# EEROS_Sensorplatine.net
KiCad netlist of a schematic drawn in Altium Designer
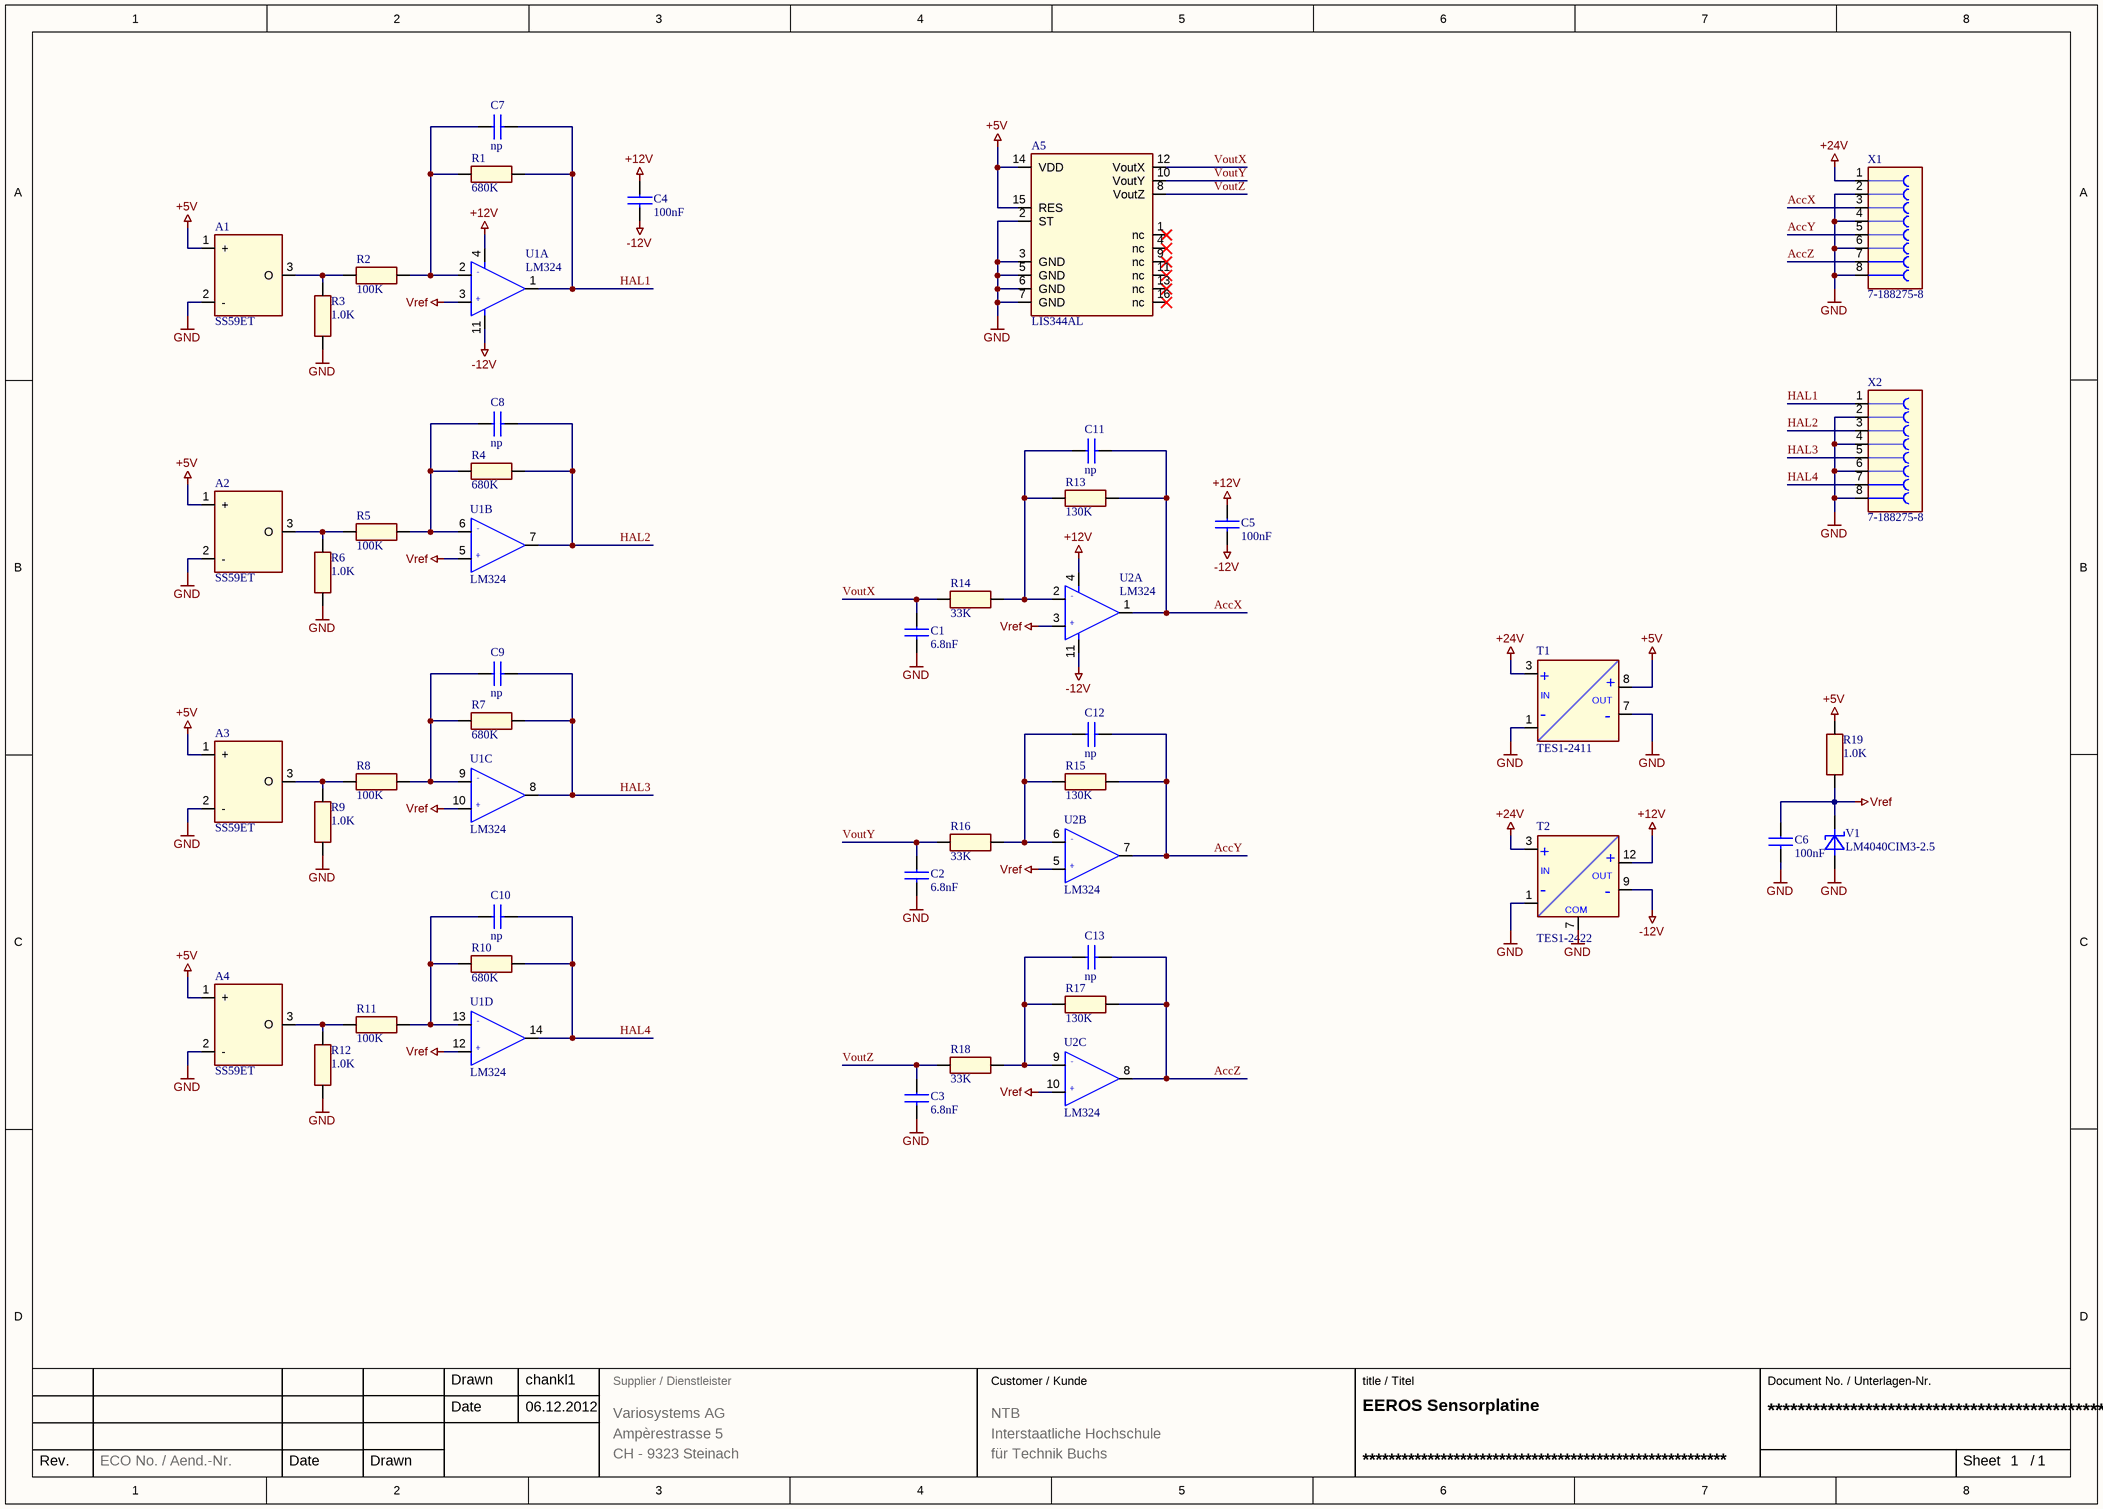
[diagram p0: EEROS_Sensorplatine.SchDoc]

(export (version "E")
  (design (tool "Eeschema 10.0.6"))
  (components
    (comp (ref "A1")
      (value "SS59ET")
      (footprint "SM/SOT89_1234")
      (description "S_ SEN MAGNE SS59ET_________________ ___")
      (fields (field (name "PART NUMBER") "2024317") (field (name "MANUFACTURER") "Honeywell"))
      (libsource (lib "Database") (part "SS59ET"))
    )
    (comp (ref "A2")
      (value "SS59ET")
      (footprint "SM/SOT89_1234")
      (description "S_ SEN MAGNE SS59ET_________________ ___")
      (fields (field (name "PART NUMBER") "2024317") (field (name "MANUFACTURER") "Honeywell"))
      (libsource (lib "Database") (part "SS59ET"))
    )
    (comp (ref "A3")
      (value "SS59ET")
      (footprint "SM/SOT89_1234")
      (description "S_ SEN MAGNE SS59ET_________________ ___")
      (fields (field (name "PART NUMBER") "2024317") (field (name "MANUFACTURER") "Honeywell"))
      (libsource (lib "Database") (part "SS59ET"))
    )
    (comp (ref "A4")
      (value "SS59ET")
      (footprint "SM/SOT89_1234")
      (description "S_ SEN MAGNE SS59ET_________________ ___")
      (fields (field (name "PART NUMBER") "2024317") (field (name "MANUFACTURER") "Honeywell"))
      (libsource (lib "Database") (part "SS59ET"))
    )
    (comp (ref "A5")
      (value "LIS344AL")
      (footprint "QFN.65M/16/WG4.00")
      (description "S_ SEN ACCEL LIS344AL_______________ ___")
      (fields (field (name "PART NUMBER") "2024318") (field (name "MANUFACTURER") "STMicrolectronics"))
      (libsource (lib "Database") (part "LIS344AL"))
    )
    (comp (ref "C1")
      (value "6.8nF")
      (footprint "VS-CAPACITORS-000A:SM/C_0603_REFLOW")
      (description "SC CAP __0603 __6n80 _50V ___10% X7R ___")
      (fields (field (name "PART NUMBER") "239551") (field (name "VOLTAGE") "50V"))
      (libsource (lib "Database") (part "CAP NP"))
    )
    (comp (ref "C2")
      (value "6.8nF")
      (footprint "VS-CAPACITORS-000A:SM/C_0603_REFLOW")
      (description "SC CAP __0603 __6n80 _50V ___10% X7R ___")
      (fields (field (name "PART NUMBER") "239551") (field (name "VOLTAGE") "50V"))
      (libsource (lib "Database") (part "CAP NP"))
    )
    (comp (ref "C3")
      (value "6.8nF")
      (footprint "VS-CAPACITORS-000A:SM/C_0603_REFLOW")
      (description "SC CAP __0603 __6n80 _50V ___10% X7R ___")
      (fields (field (name "PART NUMBER") "239551") (field (name "VOLTAGE") "50V"))
      (libsource (lib "Database") (part "CAP NP"))
    )
    (comp (ref "C4")
      (value "100nF")
      (footprint "VS-CAPACITORS-000A:SM/C_0603_REFLOW")
      (description "SC CAP __0603 100N00 _25V 80/20% Y5V ___")
      (fields (field (name "PART NUMBER") "208013") (field (name "VOLTAGE") "25V"))
      (libsource (lib "Database") (part "CAP NP"))
    )
    (comp (ref "C5")
      (value "100nF")
      (footprint "VS-CAPACITORS-000A:SM/C_0603_REFLOW")
      (description "SC CAP __0603 100N00 _25V 80/20% Y5V ___")
      (fields (field (name "PART NUMBER") "208013") (field (name "VOLTAGE") "25V"))
      (libsource (lib "Database") (part "CAP NP"))
    )
    (comp (ref "C6")
      (value "100nF")
      (footprint "VS-CAPACITORS-000A:SM/C_0603_REFLOW")
      (description "SC CAP __0603 100N00 _25V 80/20% Y5V ___")
      (fields (field (name "PART NUMBER") "208013") (field (name "VOLTAGE") "25V"))
      (libsource (lib "Database") (part "CAP NP"))
    )
    (comp (ref "C7")
      (value "np")
      (footprint "VS-CAPACITORS-000A:SM/C_0603_REFLOW")
      (libsource (lib "VS-CAPACITORS-000A") (part "CAP NP"))
    )
    (comp (ref "C8")
      (value "np")
      (footprint "VS-CAPACITORS-000A:SM/C_0603_REFLOW")
      (libsource (lib "VS-CAPACITORS-000A") (part "CAP NP"))
    )
    (comp (ref "C9")
      (value "np")
      (footprint "VS-CAPACITORS-000A:SM/C_0603_REFLOW")
      (libsource (lib "VS-CAPACITORS-000A") (part "CAP NP"))
    )
    (comp (ref "C10")
      (value "np")
      (footprint "VS-CAPACITORS-000A:SM/C_0603_REFLOW")
      (libsource (lib "VS-CAPACITORS-000A") (part "CAP NP"))
    )
    (comp (ref "C11")
      (value "np")
      (footprint "VS-CAPACITORS-000A:SM/C_0603_REFLOW")
      (libsource (lib "VS-CAPACITORS-000A") (part "CAP NP"))
    )
    (comp (ref "C12")
      (value "np")
      (footprint "VS-CAPACITORS-000A:SM/C_0603_REFLOW")
      (libsource (lib "VS-CAPACITORS-000A") (part "CAP NP"))
    )
    (comp (ref "C13")
      (value "np")
      (footprint "VS-CAPACITORS-000A:SM/C_0603_REFLOW")
      (libsource (lib "VS-CAPACITORS-000A") (part "CAP NP"))
    )
    (comp (ref "R1")
      (value "680K")
      (footprint "VS-PASSIVES-000A:SM/R_0603_REFLOW")
      (description "SC RES __0603 680K00 __0W1 ___1% T100 __")
      (fields (field (name "PART NUMBER") "226186") (field (name "POWER") "0.1W"))
      (libsource (lib "Database") (part "R-DIN"))
    )
    (comp (ref "R2")
      (value "100K")
      (footprint "VS-PASSIVES-000A:SM/R_0603_REFLOW")
      (description "SC RES __0603 100K00 __0W1 ___1% T100 __")
      (fields (field (name "PART NUMBER") "200141") (field (name "POWER") "0.1W"))
      (libsource (lib "Database") (part "R-DIN"))
    )
    (comp (ref "R3")
      (value "1.0K")
      (footprint "VS-PASSIVES-000A:SM/R_0603_REFLOW")
      (description "SC RES __0603 __1K00 __0W1 ___1% T100 __")
      (fields (field (name "PART NUMBER") "200139") (field (name "POWER") "0.1W"))
      (libsource (lib "") (part "R-DIN_1"))
    )
    (comp (ref "R4")
      (value "680K")
      (footprint "VS-PASSIVES-000A:SM/R_0603_REFLOW")
      (description "SC RES __0603 680K00 __0W1 ___1% T100 __")
      (fields (field (name "PART NUMBER") "226186") (field (name "POWER") "0.1W"))
      (libsource (lib "Database") (part "R-DIN"))
    )
    (comp (ref "R5")
      (value "100K")
      (footprint "VS-PASSIVES-000A:SM/R_0603_REFLOW")
      (description "SC RES __0603 100K00 __0W1 ___1% T100 __")
      (fields (field (name "PART NUMBER") "200141") (field (name "POWER") "0.1W"))
      (libsource (lib "Database") (part "R-DIN"))
    )
    (comp (ref "R6")
      (value "1.0K")
      (footprint "VS-PASSIVES-000A:SM/R_0603_REFLOW")
      (description "SC RES __0603 __1K00 __0W1 ___1% T100 __")
      (fields (field (name "PART NUMBER") "200139") (field (name "POWER") "0.1W"))
      (libsource (lib "") (part "R-DIN_1"))
    )
    (comp (ref "R7")
      (value "680K")
      (footprint "VS-PASSIVES-000A:SM/R_0603_REFLOW")
      (description "SC RES __0603 680K00 __0W1 ___1% T100 __")
      (fields (field (name "PART NUMBER") "226186") (field (name "POWER") "0.1W"))
      (libsource (lib "Database") (part "R-DIN"))
    )
    (comp (ref "R8")
      (value "100K")
      (footprint "VS-PASSIVES-000A:SM/R_0603_REFLOW")
      (description "SC RES __0603 100K00 __0W1 ___1% T100 __")
      (fields (field (name "PART NUMBER") "200141") (field (name "POWER") "0.1W"))
      (libsource (lib "Database") (part "R-DIN"))
    )
    (comp (ref "R9")
      (value "1.0K")
      (footprint "VS-PASSIVES-000A:SM/R_0603_REFLOW")
      (description "SC RES __0603 __1K00 __0W1 ___1% T100 __")
      (fields (field (name "PART NUMBER") "200139") (field (name "POWER") "0.1W"))
      (libsource (lib "") (part "R-DIN_1"))
    )
    (comp (ref "R10")
      (value "680K")
      (footprint "VS-PASSIVES-000A:SM/R_0603_REFLOW")
      (description "SC RES __0603 680K00 __0W1 ___1% T100 __")
      (fields (field (name "PART NUMBER") "226186") (field (name "POWER") "0.1W"))
      (libsource (lib "Database") (part "R-DIN"))
    )
    (comp (ref "R11")
      (value "100K")
      (footprint "VS-PASSIVES-000A:SM/R_0603_REFLOW")
      (description "SC RES __0603 100K00 __0W1 ___1% T100 __")
      (fields (field (name "PART NUMBER") "200141") (field (name "POWER") "0.1W"))
      (libsource (lib "Database") (part "R-DIN"))
    )
    (comp (ref "R12")
      (value "1.0K")
      (footprint "VS-PASSIVES-000A:SM/R_0603_REFLOW")
      (description "SC RES __0603 __1K00 __0W1 ___1% T100 __")
      (fields (field (name "PART NUMBER") "200139") (field (name "POWER") "0.1W"))
      (libsource (lib "") (part "R-DIN_1"))
    )
    (comp (ref "R13")
      (value "130K")
      (footprint "VS-PASSIVES-000A:SM/R_0603_REFLOW")
      (description "SC RES __0603 130K00 __0W1 ___1% T100 __")
      (fields (field (name "PART NUMBER") "240657") (field (name "POWER") "0.1W"))
      (libsource (lib "Database") (part "R-DIN"))
    )
    (comp (ref "R14")
      (value "33K")
      (footprint "VS-PASSIVES-000A:SM/R_0603_REFLOW")
      (description "SC RES __0603 _33K00 __0W1 ___1% T100 __")
      (fields (field (name "PART NUMBER") "204505") (field (name "POWER") "0.1W"))
      (libsource (lib "Database") (part "R-DIN"))
    )
    (comp (ref "R15")
      (value "130K")
      (footprint "VS-PASSIVES-000A:SM/R_0603_REFLOW")
      (description "SC RES __0603 130K00 __0W1 ___1% T100 __")
      (fields (field (name "PART NUMBER") "240657") (field (name "POWER") "0.1W"))
      (libsource (lib "Database") (part "R-DIN"))
    )
    (comp (ref "R16")
      (value "33K")
      (footprint "VS-PASSIVES-000A:SM/R_0603_REFLOW")
      (description "SC RES __0603 _33K00 __0W1 ___1% T100 __")
      (fields (field (name "PART NUMBER") "204505") (field (name "POWER") "0.1W"))
      (libsource (lib "Database") (part "R-DIN"))
    )
    (comp (ref "R17")
      (value "130K")
      (footprint "VS-PASSIVES-000A:SM/R_0603_REFLOW")
      (description "SC RES __0603 130K00 __0W1 ___1% T100 __")
      (fields (field (name "PART NUMBER") "240657") (field (name "POWER") "0.1W"))
      (libsource (lib "Database") (part "R-DIN"))
    )
    (comp (ref "R18")
      (value "33K")
      (footprint "VS-PASSIVES-000A:SM/R_0603_REFLOW")
      (description "SC RES __0603 _33K00 __0W1 ___1% T100 __")
      (fields (field (name "PART NUMBER") "204505") (field (name "POWER") "0.1W"))
      (libsource (lib "Database") (part "R-DIN"))
    )
    (comp (ref "R19")
      (value "1.0K")
      (footprint "VS-PASSIVES-000A:SM/R_0603_REFLOW")
      (description "SC RES __0603 __1K00 __0W1 ___1% T100 __")
      (fields (field (name "PART NUMBER") "200139") (field (name "POWER") "0.1W"))
      (libsource (lib "") (part "R-DIN_1"))
    )
    (comp (ref "T1")
      (value "TES1-2411")
      (footprint "TES1_SINGLE")
      (description "SS CNV TES1-2411________ _____5V _1W0 DD")
      (fields (field (name "PART NUMBER") "2024319") (field (name "MANUFACTURER") "Traco"))
      (libsource (lib "Database") (part "DC-DC_TES1_Single"))
    )
    (comp (ref "T2")
      (value "TES1-2422")
      (footprint "TES1_DUAL")
      (description "SD CNV TES1-2422________ _+/-12V _1W0 DD")
      (fields (field (name "PART NUMBER") "2024320") (field (name "MANUFACTURER") "Traco"))
      (libsource (lib "Database") (part "DC-DC_TES1_Dual"))
    )
    (comp (ref "U1")
      (value "LM324")
      (footprint "SOG.050/14/WG.244/L.350")
      (description "S_ IC_ _____SO14 LM324M*/NOPB________ __")
      (fields (field (name "PART NUMBER") "204061") (field (name "MANUFACTURER") "National Semiconductor"))
      (libsource (lib "Database") (part "LM324"))
    )
    (comp (ref "U2")
      (value "LM324")
      (footprint "SOG.050/14/WG.244/L.350")
      (description "S_ IC_ _____SO14 LM324M*/NOPB________ __")
      (fields (field (name "PART NUMBER") "204061") (field (name "MANUFACTURER") "National Semiconductor"))
      (libsource (lib "Database") (part "LM324"))
    )
    (comp (ref "V1")
      (value "LM4040CIM3-2.5")
      (footprint "SM/SOT23_123")
      (description "S_ IC_ ____SOT23 LM4040CIM3-2.5/NOPB_ __")
      (fields (field (name "PART NUMBER") "206446") (field (name "MANUFACTURER") "National Semiconductor"))
      (libsource (lib "Database") (part "DIODE_REF_2P"))
    )
    (comp (ref "X1")
      (value "7-188275-8")
      (footprint "MICRO-MATCH_8P_SMD")
      (description "S_ CON F ST ____ ___8P ____ __ R1.27 ___")
      (fields (field (name "PART NUMBER") "249627") (field (name "MANUFACTURER") "AMP Inc."))
      (libsource (lib "Database") (part "CON8F"))
    )
    (comp (ref "X2")
      (value "7-188275-8")
      (footprint "MICRO-MATCH_8P_SMD")
      (description "S_ CON F ST ____ ___8P ____ __ R1.27 ___")
      (fields (field (name "PART NUMBER") "249627") (field (name "MANUFACTURER") "AMP Inc."))
      (libsource (lib "Database") (part "CON8F"))
    )
  )
  (nets
    (net (code "1") (name "+5V") (class "Default")
      (node (ref "A1") (pin "1") (pinfunction "+_1") (pintype "passive"))
      (node (ref "A2") (pin "1") (pinfunction "+_1") (pintype "passive"))
      (node (ref "A3") (pin "1") (pinfunction "+_1") (pintype "passive"))
      (node (ref "A4") (pin "1") (pinfunction "+_1") (pintype "passive"))
      (node (ref "A5") (pin "14") (pinfunction "VDD_14") (pintype "passive"))
      (node (ref "A5") (pin "15") (pinfunction "RES_15") (pintype "passive"))
      (node (ref "R19") (pin "1") (pinfunction "1_1") (pintype "passive"))
      (node (ref "T1") (pin "8") (pinfunction "8_8") (pintype "passive"))
    )
    (net (code "2") (name "+12V") (class "Default")
      (node (ref "C4") (pin "1") (pinfunction "1_1") (pintype "passive"))
      (node (ref "C5") (pin "1") (pinfunction "1_1") (pintype "passive"))
      (node (ref "T2") (pin "12") (pinfunction "12_12") (pintype "passive"))
      (node (ref "U1") (pin "4") (pinfunction "VCC_4") (pintype "passive"))
      (node (ref "U2") (pin "4") (pinfunction "VCC_4") (pintype "passive"))
    )
    (net (code "3") (name "+24V") (class "Default")
      (node (ref "T1") (pin "3") (pinfunction "3_3") (pintype "passive"))
      (node (ref "T2") (pin "3") (pinfunction "3_3") (pintype "passive"))
      (node (ref "X1") (pin "1") (pinfunction "1_1") (pintype "passive"))
    )
    (net (code "4") (name "-12V") (class "Default")
      (node (ref "C4") (pin "2") (pinfunction "2_2") (pintype "passive"))
      (node (ref "C5") (pin "2") (pinfunction "2_2") (pintype "passive"))
      (node (ref "T2") (pin "9") (pinfunction "9_9") (pintype "passive"))
      (node (ref "U1") (pin "11") (pinfunction "GND_11") (pintype "passive"))
      (node (ref "U2") (pin "11") (pinfunction "GND_11") (pintype "passive"))
    )
    (net (code "5") (name "/AccX") (class "Default")
      (node (ref "C11") (pin "2") (pinfunction "2_2") (pintype "passive"))
      (node (ref "R13") (pin "2") (pinfunction "2_2") (pintype "passive"))
      (node (ref "U2") (pin "1") (pinfunction "OUT_1") (pintype "passive"))
      (node (ref "X1") (pin "3") (pinfunction "3_3") (pintype "passive"))
    )
    (net (code "6") (name "/AccY") (class "Default")
      (node (ref "C12") (pin "2") (pinfunction "2_2") (pintype "passive"))
      (node (ref "R15") (pin "2") (pinfunction "2_2") (pintype "passive"))
      (node (ref "U2") (pin "7") (pinfunction "OUT_7") (pintype "passive"))
      (node (ref "X1") (pin "5") (pinfunction "5_5") (pintype "passive"))
    )
    (net (code "7") (name "/AccZ") (class "Default")
      (node (ref "C13") (pin "2") (pinfunction "2_2") (pintype "passive"))
      (node (ref "R17") (pin "2") (pinfunction "2_2") (pintype "passive"))
      (node (ref "U2") (pin "8") (pinfunction "OUT_8") (pintype "passive"))
      (node (ref "X1") (pin "7") (pinfunction "7_7") (pintype "passive"))
    )
    (net (code "8") (name "/HAL1") (class "Default")
      (node (ref "C7") (pin "2") (pinfunction "2_2") (pintype "passive"))
      (node (ref "R1") (pin "2") (pinfunction "2_2") (pintype "passive"))
      (node (ref "U1") (pin "1") (pinfunction "OUT_1") (pintype "passive"))
      (node (ref "X2") (pin "1") (pinfunction "1_1") (pintype "passive"))
    )
    (net (code "9") (name "/HAL2") (class "Default")
      (node (ref "C8") (pin "2") (pinfunction "2_2") (pintype "passive"))
      (node (ref "R4") (pin "2") (pinfunction "2_2") (pintype "passive"))
      (node (ref "U1") (pin "7") (pinfunction "OUT_7") (pintype "passive"))
      (node (ref "X2") (pin "3") (pinfunction "3_3") (pintype "passive"))
    )
    (net (code "10") (name "/HAL3") (class "Default")
      (node (ref "C9") (pin "2") (pinfunction "2_2") (pintype "passive"))
      (node (ref "R7") (pin "2") (pinfunction "2_2") (pintype "passive"))
      (node (ref "U1") (pin "8") (pinfunction "OUT_8") (pintype "passive"))
      (node (ref "X2") (pin "5") (pinfunction "5_5") (pintype "passive"))
    )
    (net (code "11") (name "/HAL4") (class "Default")
      (node (ref "C10") (pin "2") (pinfunction "2_2") (pintype "passive"))
      (node (ref "R10") (pin "2") (pinfunction "2_2") (pintype "passive"))
      (node (ref "U1") (pin "14") (pinfunction "OUT_14") (pintype "passive"))
      (node (ref "X2") (pin "7") (pinfunction "7_7") (pintype "passive"))
    )
    (net (code "12") (name "/VoutX") (class "Default")
      (node (ref "A5") (pin "12") (pinfunction "VoutX_12") (pintype "passive"))
      (node (ref "C1") (pin "1") (pinfunction "1_1") (pintype "passive"))
      (node (ref "R14") (pin "1") (pinfunction "1_1") (pintype "passive"))
    )
    (net (code "13") (name "/VoutY") (class "Default")
      (node (ref "A5") (pin "10") (pinfunction "VoutY_10") (pintype "passive"))
      (node (ref "C2") (pin "1") (pinfunction "1_1") (pintype "passive"))
      (node (ref "R16") (pin "1") (pinfunction "1_1") (pintype "passive"))
    )
    (net (code "14") (name "/VoutZ") (class "Default")
      (node (ref "A5") (pin "8") (pinfunction "VoutZ_8") (pintype "passive"))
      (node (ref "C3") (pin "1") (pinfunction "1_1") (pintype "passive"))
      (node (ref "R18") (pin "1") (pinfunction "1_1") (pintype "passive"))
    )
    (net (code "15") (name "GND") (class "Default")
      (node (ref "A1") (pin "2") (pinfunction "-_2") (pintype "passive"))
      (node (ref "A2") (pin "2") (pinfunction "-_2") (pintype "passive"))
      (node (ref "A3") (pin "2") (pinfunction "-_2") (pintype "passive"))
      (node (ref "A4") (pin "2") (pinfunction "-_2") (pintype "passive"))
      (node (ref "A5") (pin "2") (pinfunction "ST_2") (pintype "passive"))
      (node (ref "A5") (pin "3") (pinfunction "GND_3") (pintype "passive"))
      (node (ref "A5") (pin "5") (pinfunction "GND_5") (pintype "passive"))
      (node (ref "A5") (pin "6") (pinfunction "GND_6") (pintype "passive"))
      (node (ref "A5") (pin "7") (pinfunction "GND_7") (pintype "passive"))
      (node (ref "C1") (pin "2") (pinfunction "2_2") (pintype "passive"))
      (node (ref "C2") (pin "2") (pinfunction "2_2") (pintype "passive"))
      (node (ref "C3") (pin "2") (pinfunction "2_2") (pintype "passive"))
      (node (ref "C6") (pin "2") (pinfunction "2_2") (pintype "passive"))
      (node (ref "R12") (pin "2") (pinfunction "2_2") (pintype "passive"))
      (node (ref "R3") (pin "2") (pinfunction "2_2") (pintype "passive"))
      (node (ref "R6") (pin "2") (pinfunction "2_2") (pintype "passive"))
      (node (ref "R9") (pin "2") (pinfunction "2_2") (pintype "passive"))
      (node (ref "T1") (pin "1") (pinfunction "1_1") (pintype "passive"))
      (node (ref "T1") (pin "7") (pinfunction "7_7") (pintype "passive"))
      (node (ref "T2") (pin "1") (pinfunction "1_1") (pintype "passive"))
      (node (ref "T2") (pin "7") (pinfunction "7_7") (pintype "passive"))
      (node (ref "V1") (pin "2") (pinfunction "A_2") (pintype "passive"))
      (node (ref "X1") (pin "2") (pinfunction "2_2") (pintype "passive"))
      (node (ref "X1") (pin "4") (pinfunction "4_4") (pintype "passive"))
      (node (ref "X1") (pin "6") (pinfunction "6_6") (pintype "passive"))
      (node (ref "X1") (pin "8") (pinfunction "8_8") (pintype "passive"))
      (node (ref "X2") (pin "2") (pinfunction "2_2") (pintype "passive"))
      (node (ref "X2") (pin "4") (pinfunction "4_4") (pintype "passive"))
      (node (ref "X2") (pin "6") (pinfunction "6_6") (pintype "passive"))
      (node (ref "X2") (pin "8") (pinfunction "8_8") (pintype "passive"))
    )
    (net (code "16") (name "Net-(A1-O)") (class "Default")
      (node (ref "A1") (pin "3") (pinfunction "O_3") (pintype "passive"))
      (node (ref "R2") (pin "1") (pinfunction "1_1") (pintype "passive"))
      (node (ref "R3") (pin "1") (pinfunction "1_1") (pintype "passive"))
    )
    (net (code "17") (name "Net-(A2-O)") (class "Default")
      (node (ref "A2") (pin "3") (pinfunction "O_3") (pintype "passive"))
      (node (ref "R5") (pin "1") (pinfunction "1_1") (pintype "passive"))
      (node (ref "R6") (pin "1") (pinfunction "1_1") (pintype "passive"))
    )
    (net (code "18") (name "Net-(A3-O)") (class "Default")
      (node (ref "A3") (pin "3") (pinfunction "O_3") (pintype "passive"))
      (node (ref "R8") (pin "1") (pinfunction "1_1") (pintype "passive"))
      (node (ref "R9") (pin "1") (pinfunction "1_1") (pintype "passive"))
    )
    (net (code "19") (name "Net-(A4-O)") (class "Default")
      (node (ref "A4") (pin "3") (pinfunction "O_3") (pintype "passive"))
      (node (ref "R11") (pin "1") (pinfunction "1_1") (pintype "passive"))
      (node (ref "R12") (pin "1") (pinfunction "1_1") (pintype "passive"))
    )
    (net (code "20") (name "Net-(U1A--IN)") (class "Default")
      (node (ref "C7") (pin "1") (pinfunction "1_1") (pintype "passive"))
      (node (ref "R1") (pin "1") (pinfunction "1_1") (pintype "passive"))
      (node (ref "R2") (pin "2") (pinfunction "2_2") (pintype "passive"))
      (node (ref "U1") (pin "2") (pinfunction "-IN_2") (pintype "passive"))
    )
    (net (code "21") (name "Net-(U1B--IN)") (class "Default")
      (node (ref "C8") (pin "1") (pinfunction "1_1") (pintype "passive"))
      (node (ref "R4") (pin "1") (pinfunction "1_1") (pintype "passive"))
      (node (ref "R5") (pin "2") (pinfunction "2_2") (pintype "passive"))
      (node (ref "U1") (pin "6") (pinfunction "-IN_6") (pintype "passive"))
    )
    (net (code "22") (name "Net-(U1C--IN)") (class "Default")
      (node (ref "C9") (pin "1") (pinfunction "1_1") (pintype "passive"))
      (node (ref "R7") (pin "1") (pinfunction "1_1") (pintype "passive"))
      (node (ref "R8") (pin "2") (pinfunction "2_2") (pintype "passive"))
      (node (ref "U1") (pin "9") (pinfunction "-IN_9") (pintype "passive"))
    )
    (net (code "23") (name "Net-(U1D--IN)") (class "Default")
      (node (ref "C10") (pin "1") (pinfunction "1_1") (pintype "passive"))
      (node (ref "R10") (pin "1") (pinfunction "1_1") (pintype "passive"))
      (node (ref "R11") (pin "2") (pinfunction "2_2") (pintype "passive"))
      (node (ref "U1") (pin "13") (pinfunction "-IN_13") (pintype "passive"))
    )
    (net (code "24") (name "Net-(U2A--IN)") (class "Default")
      (node (ref "C11") (pin "1") (pinfunction "1_1") (pintype "passive"))
      (node (ref "R13") (pin "1") (pinfunction "1_1") (pintype "passive"))
      (node (ref "R14") (pin "2") (pinfunction "2_2") (pintype "passive"))
      (node (ref "U2") (pin "2") (pinfunction "-IN_2") (pintype "passive"))
    )
    (net (code "25") (name "Net-(U2B--IN)") (class "Default")
      (node (ref "C12") (pin "1") (pinfunction "1_1") (pintype "passive"))
      (node (ref "R15") (pin "1") (pinfunction "1_1") (pintype "passive"))
      (node (ref "R16") (pin "2") (pinfunction "2_2") (pintype "passive"))
      (node (ref "U2") (pin "6") (pinfunction "-IN_6") (pintype "passive"))
    )
    (net (code "26") (name "Net-(U2C--IN)") (class "Default")
      (node (ref "C13") (pin "1") (pinfunction "1_1") (pintype "passive"))
      (node (ref "R17") (pin "1") (pinfunction "1_1") (pintype "passive"))
      (node (ref "R18") (pin "2") (pinfunction "2_2") (pintype "passive"))
      (node (ref "U2") (pin "9") (pinfunction "-IN_9") (pintype "passive"))
    )
    (net (code "27") (name "Vref") (class "Default")
      (node (ref "C6") (pin "1") (pinfunction "1_1") (pintype "passive"))
      (node (ref "R19") (pin "2") (pinfunction "2_2") (pintype "passive"))
      (node (ref "U1") (pin "10") (pinfunction "+IN_10") (pintype "passive"))
      (node (ref "U1") (pin "12") (pinfunction "+IN_12") (pintype "passive"))
      (node (ref "U1") (pin "3") (pinfunction "+IN_3") (pintype "passive"))
      (node (ref "U1") (pin "5") (pinfunction "+IN_5") (pintype "passive"))
      (node (ref "U2") (pin "10") (pinfunction "+IN_10") (pintype "passive"))
      (node (ref "U2") (pin "3") (pinfunction "+IN_3") (pintype "passive"))
      (node (ref "U2") (pin "5") (pinfunction "+IN_5") (pintype "passive"))
      (node (ref "V1") (pin "1") (pinfunction "K_1") (pintype "passive"))
    )
    (net (code "28") (name "unconnected-(A5-nc-Pad1)") (class "Default")
      (node (ref "A5") (pin "1") (pinfunction "nc_1") (pintype "passive+no_connect"))
    )
    (net (code "29") (name "unconnected-(A5-nc-Pad4)") (class "Default")
      (node (ref "A5") (pin "4") (pinfunction "nc_4") (pintype "passive+no_connect"))
    )
    (net (code "30") (name "unconnected-(A5-nc-Pad9)") (class "Default")
      (node (ref "A5") (pin "9") (pinfunction "nc_9") (pintype "passive+no_connect"))
    )
    (net (code "31") (name "unconnected-(A5-nc-Pad11)") (class "Default")
      (node (ref "A5") (pin "11") (pinfunction "nc_11") (pintype "passive+no_connect"))
    )
    (net (code "32") (name "unconnected-(A5-nc-Pad13)") (class "Default")
      (node (ref "A5") (pin "13") (pinfunction "nc_13") (pintype "passive+no_connect"))
    )
    (net (code "33") (name "unconnected-(A5-nc-Pad16)") (class "Default")
      (node (ref "A5") (pin "16") (pinfunction "nc_16") (pintype "passive+no_connect"))
    )
  )
)
